# ATTinySchematic.net
KiCad netlist of a schematic drawn in Altium Designer
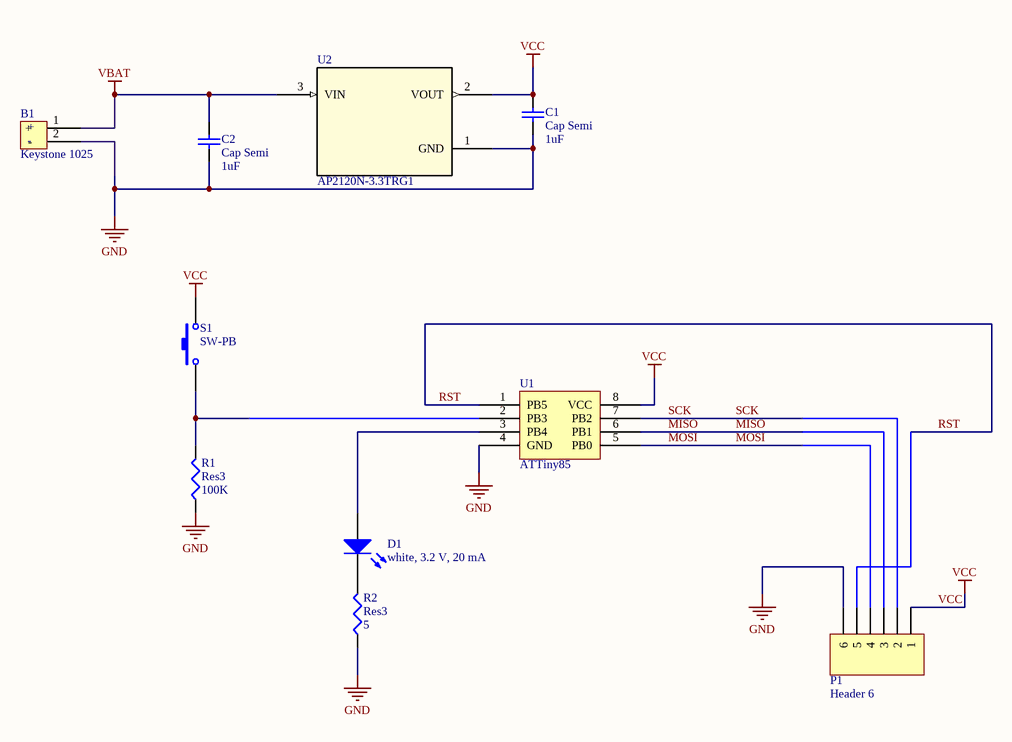
[diagram p0: ATTinySchematic.SchDoc]

(export (version "E")
  (design (tool "Eeschema 10.0.6"))
  (components
    (comp (ref "B1")
      (value "Keystone 1025")
      (footprint "1025")
      (description "BATT HOLDER COIN 1/2 CELL PC PIN")
      (libsource (lib "lightSCHLib") (part "Keystone 1025"))
    )
    (comp (ref "C1")
      (value "Cap Semi")
      (footprint "1608[0603]")
      (description "Capacitor (Semiconductor SIM Model)")
      (fields (field (name "ALTIUM_VALUE") "1uF") (field (name "PUBLISHER") "Altium Limited"))
      (libsource (lib "Miscellaneous Devices") (part "Cap Semi"))
    )
    (comp (ref "C2")
      (value "Cap Semi")
      (footprint "1608[0603]")
      (description "Capacitor (Semiconductor SIM Model)")
      (fields (field (name "ALTIUM_VALUE") "1uF") (field (name "PUBLISHER") "Altium Limited"))
      (libsource (lib "Miscellaneous Devices") (part "Cap Semi"))
    )
    (comp (ref "D1")
      (value "white, 3.2 V, 20 mA")
      (footprint "HDR1X2")
      (description "Typical RED, GREEN, YELLOW, AMBER GaAs LED")
      (fields (field (name "PUBLISHER") "Altium Limited"))
      (libsource (lib "lightSCHLib") (part "LED2"))
    )
    (comp (ref "P1")
      (value "Header 6")
      (footprint "HDR1X6")
      (description "Header, 6-Pin")
      (fields (field (name "PUBLISHER") "Altium Limited"))
      (libsource (lib "Miscellaneous Connectors") (part "Header 6"))
    )
    (comp (ref "R1")
      (value "Res3")
      (footprint "J1-0603")
      (description "Resistor")
      (fields (field (name "ALTIUM_VALUE") "100K") (field (name "PUBLISHER") "Altium Limited"))
      (libsource (lib "Miscellaneous Devices") (part "Res3"))
    )
    (comp (ref "R2")
      (value "Res3")
      (footprint "J1-0603")
      (description "Resistor")
      (fields (field (name "ALTIUM_VALUE") "5") (field (name "PUBLISHER") "Altium Limited"))
      (libsource (lib "Miscellaneous Devices") (part "Res3"))
    )
    (comp (ref "S1")
      (value "SW-PB")
      (footprint "SPST-2")
      (description "Switch")
      (fields (field (name "PUBLISHER") "Altium Limited"))
      (libsource (lib "Miscellaneous Devices") (part "SW-PB"))
    )
    (comp (ref "U1") (value "ATTiny85") (footprint "8S2") (libsource (lib "ATTinySch") (part "ATTiny85")))
    (comp (ref "U2")
      (value "AP2120N-3.3TRG1")
      (footprint "SOT-23")
      (description "IC REG LINEAR 3.3V 150MA SOT23")
      (libsource (lib "lightSCHLib") (part "AP2120N-3.3TRG1"))
    )
  )
  (nets
    (net (code "1") (name "/MISO") (class "Default")
      (node (ref "P1") (pin "3") (pinfunction "3_3") (pintype "passive"))
      (node (ref "U1") (pin "6") (pinfunction "PB1_6") (pintype "passive"))
    )
    (net (code "2") (name "/MOSI") (class "Default")
      (node (ref "P1") (pin "4") (pinfunction "4_4") (pintype "passive"))
      (node (ref "U1") (pin "5") (pinfunction "PB0_5") (pintype "passive"))
    )
    (net (code "3") (name "/RST") (class "Default")
      (node (ref "P1") (pin "5") (pinfunction "5_5") (pintype "passive"))
      (node (ref "U1") (pin "1") (pinfunction "PB5_1") (pintype "passive"))
    )
    (net (code "4") (name "/SCK") (class "Default")
      (node (ref "P1") (pin "2") (pinfunction "2_2") (pintype "passive"))
      (node (ref "U1") (pin "7") (pinfunction "PB2_7") (pintype "passive"))
    )
    (net (code "5") (name "GND") (class "Default")
      (node (ref "B1") (pin "2") (pinfunction "-_2") (pintype "passive"))
      (node (ref "C1") (pin "1") (pinfunction "1_1") (pintype "passive"))
      (node (ref "C2") (pin "1") (pinfunction "1_1") (pintype "passive"))
      (node (ref "P1") (pin "6") (pinfunction "6_6") (pintype "passive"))
      (node (ref "R1") (pin "1") (pinfunction "1_1") (pintype "passive"))
      (node (ref "R2") (pin "1") (pinfunction "1_1") (pintype "passive"))
      (node (ref "U1") (pin "4") (pinfunction "GND_4") (pintype "passive"))
      (node (ref "U2") (pin "1") (pinfunction "GND_1") (pintype "power_in"))
    )
    (net (code "6") (name "Net-(D1-A)") (class "Default")
      (node (ref "D1") (pin "1") (pinfunction "A_1") (pintype "passive"))
      (node (ref "R2") (pin "2") (pinfunction "2_2") (pintype "passive"))
    )
    (net (code "7") (name "Net-(D1-K)") (class "Default")
      (node (ref "D1") (pin "2") (pinfunction "K_2") (pintype "passive"))
      (node (ref "U1") (pin "3") (pinfunction "PB4_3") (pintype "passive"))
    )
    (net (code "8") (name "Net-(U1-PB3)") (class "Default")
      (node (ref "R1") (pin "2") (pinfunction "2_2") (pintype "passive"))
      (node (ref "S1") (pin "1") (pinfunction "1_1") (pintype "passive"))
      (node (ref "U1") (pin "2") (pinfunction "PB3_2") (pintype "passive"))
    )
    (net (code "9") (name "VBAT") (class "Default")
      (node (ref "B1") (pin "1") (pinfunction "+_1") (pintype "passive"))
      (node (ref "C2") (pin "2") (pinfunction "2_2") (pintype "passive"))
      (node (ref "U2") (pin "3") (pinfunction "VIN_3") (pintype "input"))
    )
    (net (code "10") (name "VCC") (class "Default")
      (node (ref "C1") (pin "2") (pinfunction "2_2") (pintype "passive"))
      (node (ref "P1") (pin "1") (pinfunction "1_1") (pintype "passive"))
      (node (ref "S1") (pin "2") (pinfunction "2_2") (pintype "passive"))
      (node (ref "U1") (pin "8") (pinfunction "VCC_8") (pintype "passive"))
      (node (ref "U2") (pin "2") (pinfunction "VOUT_2") (pintype "output"))
    )
  )
)
